# filter.net
KiCad netlist of a schematic drawn in Altium Designer
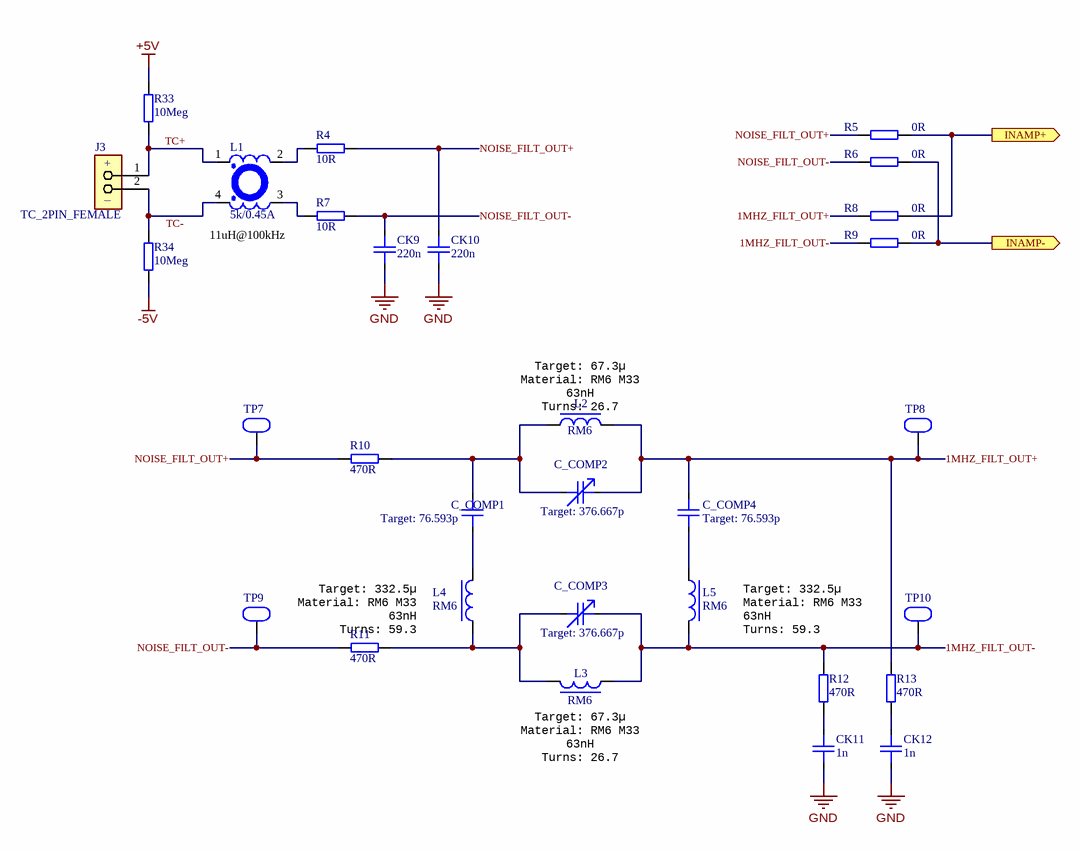
[diagram p0: filter.SchDoc]

(export (version "E")
  (design (tool "Eeschema 10.0.6"))
  (components
    (comp (ref "CK9")
      (value "220n")
      (footprint "CAPC1608X09N(SMC0603)")
      (description "C; 220n; 16V; 10%; X7R; ??;")
      (fields
        (field (name "MANUFACTURER") "TDK Corporation: C1608X7R1C224K080AC;;AVX Corporation: 0603YC224KAT2A;;Samsung: CL10B224KO8NNNC")
      )
      (libsource (lib "altium_sql") (part "CK"))
    )
    (comp (ref "CK10")
      (value "220n")
      (footprint "CAPC1608X09N(SMC0603)")
      (description "C; 220n; 16V; 10%; X7R; ??;")
      (fields
        (field (name "MANUFACTURER") "TDK Corporation: C1608X7R1C224K080AC;;AVX Corporation: 0603YC224KAT2A;;Samsung: CL10B224KO8NNNC")
      )
      (libsource (lib "altium_sql") (part "CK"))
    )
    (comp (ref "CK11")
      (value "1n")
      (footprint "CAPC2012X14N(SMC0805)")
      (description "C; 1n; 50V; 5%; NP0/C0G; ??;")
      (fields (field (name "MANUFACTURER") "YAGEO: CC0805JRNPO9BN102;;AVX: 0805 5A 102 JAT2A"))
      (libsource (lib "altium_sql") (part "CK"))
    )
    (comp (ref "CK12")
      (value "1n")
      (footprint "CAPC2012X14N(SMC0805)")
      (description "C; 1n; 50V; 5%; NP0/C0G; ??;")
      (fields (field (name "MANUFACTURER") "YAGEO: CC0805JRNPO9BN102;;AVX: 0805 5A 102 JAT2A"))
      (libsource (lib "altium_sql") (part "CK"))
    )
    (comp (ref "C_COMP1")
      (value "Target: 76.593p")
      (footprint "CAPC1005X06N(SMC0402)")
      (description "C; 470p; 50V; 1%; NP0/C0G; ??;")
      (fields (field (name "MANUFACTURER") "Kemet: C0402C471F5GAC7867;;Murata: GRM1555C1H471FA01D"))
      (libsource (lib "altium_sql") (part "CK"))
    )
    (comp (ref "C_COMP2")
      (value "Target: 376.667p")
      (footprint "CTSC3S")
      (description "3.5 - 10pF, 50V")
      (libsource (lib "custom-footprints") (part "CTSC3S"))
    )
    (comp (ref "C_COMP3")
      (value "Target: 376.667p")
      (footprint "CTSC3S")
      (description "3.5 - 10pF, 50V")
      (libsource (lib "custom-footprints") (part "CTSC3S"))
    )
    (comp (ref "C_COMP4")
      (value "Target: 76.593p")
      (footprint "CAPC1005X06N(SMC0402)")
      (description "C; 470p; 50V; 1%; NP0/C0G; ??;")
      (fields (field (name "MANUFACTURER") "Kemet: C0402C471F5GAC7867;;Murata: GRM1555C1H471FA01D"))
      (libsource (lib "altium_sql") (part "CK"))
    )
    (comp (ref "J3")
      (value "TC_2PIN_FEMALE")
      (footprint "TC_PCC-SMD")
      (description "Universal SMD thermocouple connector, 2 pin, Female")
      (libsource (lib "custom-footprints") (part "TC_2PIN_FEMALE"))
    )
    (comp (ref "L1")
      (value "5k/0.45A")
      (footprint "WE_744235110")
      (description "Flt; Common Mode Chokes; 0.8Ohm; 0.45A; 60V; 1x;")
      (fields (field (name "MANUFACTURER") "Würth: 744235110"))
      (libsource (lib "altium_sql") (part "L_COMP_43"))
    )
    (comp (ref "L2")
      (value "RM6")
      (footprint "INDP1616X10N")
      (description "L; 0.47uH; 1.7A; 30%; 0.101Ohm; Fe; 1x;")
      (fields (field (name "MANUFACTURER") "Wurth Elektronik: 784383130047"))
      (libsource (lib "altium_sql") (part "L"))
    )
    (comp (ref "L3")
      (value "RM6")
      (footprint "INDP1616X10N")
      (description "L; 0.47uH; 1.7A; 30%; 0.101Ohm; Fe; 1x;")
      (fields (field (name "MANUFACTURER") "Wurth Elektronik: 784383130047"))
      (libsource (lib "") (part "L_1"))
    )
    (comp (ref "L4")
      (value "RM6")
      (footprint "INDP1616X10N")
      (description "L; 0.47uH; 1.7A; 30%; 0.101Ohm; Fe; 1x;")
      (fields (field (name "MANUFACTURER") "Wurth Elektronik: 784383130047"))
      (libsource (lib "altium_sql") (part "L"))
    )
    (comp (ref "L5")
      (value "RM6")
      (footprint "INDP1616X10N")
      (description "L; 0.47uH; 1.7A; 30%; 0.101Ohm; Fe; 1x;")
      (fields (field (name "MANUFACTURER") "Wurth Elektronik: 784383130047"))
      (libsource (lib "") (part "L_1"))
    )
    (comp (ref "R4")
      (value "10R")
      (footprint "RESC2012X06N(SMR0805)")
      (description "R; 10R; 0.125W; 1%; 150V; Thick Film; ±200ppm/K; 1x;")
      (libsource (lib "altium_sql") (part "R"))
    )
    (comp (ref "R5")
      (value "0R")
      (footprint "RESC2012X06N(SMR0805)")
      (description "R; 0R; 0.125W; 1%; 150V; Thick Film; ±200ppm/K; 1x;")
      (fields
        (field (name "MANUFACTURER") "YAGEO: RC0805JR-100RL;;YAGEO: RC0805JR-130RL;;YAGEO: RC0805JR-070RL")
      )
      (libsource (lib "altium_sql") (part "R"))
    )
    (comp (ref "R6")
      (value "0R")
      (footprint "RESC2012X06N(SMR0805)")
      (description "R; 0R; 0.125W; 1%; 150V; Thick Film; ±200ppm/K; 1x;")
      (fields
        (field (name "MANUFACTURER") "YAGEO: RC0805JR-100RL;;YAGEO: RC0805JR-130RL;;YAGEO: RC0805JR-070RL")
      )
      (libsource (lib "altium_sql") (part "R"))
    )
    (comp (ref "R7")
      (value "10R")
      (footprint "RESC2012X06N(SMR0805)")
      (description "R; 10R; 0.125W; 1%; 150V; Thick Film; ±200ppm/K; 1x;")
      (libsource (lib "altium_sql") (part "R"))
    )
    (comp (ref "R8")
      (value "0R")
      (footprint "RESC2012X06N(SMR0805)")
      (description "R; 0R; 0.125W; 1%; 150V; Thick Film; ±200ppm/K; 1x;")
      (fields
        (field (name "MANUFACTURER") "YAGEO: RC0805JR-100RL;;YAGEO: RC0805JR-130RL;;YAGEO: RC0805JR-070RL")
      )
      (libsource (lib "altium_sql") (part "R"))
    )
    (comp (ref "R9")
      (value "0R")
      (footprint "RESC2012X06N(SMR0805)")
      (description "R; 0R; 0.125W; 1%; 150V; Thick Film; ±200ppm/K; 1x;")
      (fields
        (field (name "MANUFACTURER") "YAGEO: RC0805JR-100RL;;YAGEO: RC0805JR-130RL;;YAGEO: RC0805JR-070RL")
      )
      (libsource (lib "altium_sql") (part "R"))
    )
    (comp (ref "R10")
      (value "470R")
      (footprint "RESC1608X06N(SMR0603)")
      (description "R; 470R; 0.1W; 1%; 75V; Thick Film; ±100ppm/K; 1x;")
      (fields (field (name "MANUFACTURER") "Yageo: RC0603FR-07470RL;;Panasonic: ERJ3EKF4700V"))
      (libsource (lib "altium_sql") (part "R"))
    )
    (comp (ref "R11")
      (value "470R")
      (footprint "RESC1608X06N(SMR0603)")
      (description "R; 470R; 0.1W; 1%; 75V; Thick Film; ±100ppm/K; 1x;")
      (fields (field (name "MANUFACTURER") "Yageo: RC0603FR-07470RL;;Panasonic: ERJ3EKF4700V"))
      (libsource (lib "altium_sql") (part "R"))
    )
    (comp (ref "R12")
      (value "470R")
      (footprint "RESC1608X06N(SMR0603)")
      (description "R; 470R; 0.1W; 1%; 75V; Thick Film; ±100ppm/K; 1x;")
      (fields (field (name "MANUFACTURER") "Yageo: RC0603FR-07470RL;;Panasonic: ERJ3EKF4700V"))
      (libsource (lib "altium_sql") (part "R"))
    )
    (comp (ref "R13")
      (value "470R")
      (footprint "RESC1608X06N(SMR0603)")
      (description "R; 470R; 0.1W; 1%; 75V; Thick Film; ±100ppm/K; 1x;")
      (fields (field (name "MANUFACTURER") "Yageo: RC0603FR-07470RL;;Panasonic: ERJ3EKF4700V"))
      (libsource (lib "altium_sql") (part "R"))
    )
    (comp (ref "R33")
      (value "10Meg")
      (footprint "RESC2012X06N(SMR0805)")
      (description "R; 10Meg; 0.125W; 5%; 150V; Thick Film; ±100ppm/K; 1x;")
      (fields
        (field (name "MANUFACTURER") "YAGEO: RC0805JR-0710ML;;BC Components: MCU0805-50 1% P5 10M;;PANASONIC: ERJ 6GE Y J 106 V")
      )
      (libsource (lib "altium_sql") (part "R"))
    )
    (comp (ref "R34")
      (value "10Meg")
      (footprint "RESC2012X06N(SMR0805)")
      (description "R; 10Meg; 0.125W; 5%; 150V; Thick Film; ±100ppm/K; 1x;")
      (fields
        (field (name "MANUFACTURER") "YAGEO: RC0805JR-0710ML;;BC Components: MCU0805-50 1% P5 10M;;PANASONIC: ERJ 6GE Y J 106 V")
      )
      (libsource (lib "altium_sql") (part "R"))
    )
    (comp (ref "TP7")
      (value "Test Point")
      (footprint "SMD_Testpoint_Onelayer")
      (description "Con; Test Point; 1x; PCB; ??; ??V; ??A; ??; Tin; Contact;")
      (fields (field (name "MANUFACTURER") "Harwin: S1751-46R") (field (name "CONNECTOR_PART") "Contact"))
      (libsource (lib "altium_sql") (part "EJ+TESTPOINTXX0"))
    )
    (comp (ref "TP8")
      (value "Test Point")
      (footprint "SMD_Testpoint_Onelayer")
      (description "Con; Test Point; 1x; PCB; ??; ??V; ??A; ??; Tin; Contact;")
      (fields (field (name "MANUFACTURER") "Harwin: S1751-46R") (field (name "CONNECTOR_PART") "Contact"))
      (libsource (lib "altium_sql") (part "EJ+TESTPOINTXX0"))
    )
    (comp (ref "TP9")
      (value "Test Point")
      (footprint "SMD_Testpoint_Onelayer")
      (description "Con; Test Point; 1x; PCB; ??; ??V; ??A; ??; Tin; Contact;")
      (fields (field (name "MANUFACTURER") "Harwin: S1751-46R") (field (name "CONNECTOR_PART") "Contact"))
      (libsource (lib "altium_sql") (part "EJ+TESTPOINTXX0"))
    )
    (comp (ref "TP10")
      (value "Test Point")
      (footprint "SMD_Testpoint_Onelayer")
      (description "Con; Test Point; 1x; PCB; ??; ??V; ??A; ??; Tin; Contact;")
      (fields (field (name "MANUFACTURER") "Harwin: S1751-46R") (field (name "CONNECTOR_PART") "Contact"))
      (libsource (lib "altium_sql") (part "EJ+TESTPOINTXX0"))
    )
  )
  (nets
    (net (code "1") (name "+5V") (class "Default")
      (node (ref "R33") (pin "2") (pinfunction "2_2") (pintype "passive"))
    )
    (net (code "2") (name "-5V") (class "Default")
      (node (ref "R34") (pin "1") (pinfunction "1_1") (pintype "passive"))
    )
    (net (code "3") (name "/1MHZ_FILT_OUT+") (class "Default")
      (node (ref "C_COMP2") (pin "1") (pinfunction "1_1") (pintype "passive"))
      (node (ref "C_COMP4") (pin "1") (pinfunction "1_1") (pintype "passive"))
      (node (ref "L2") (pin "2") (pinfunction "L1B_2") (pintype "passive"))
      (node (ref "R13") (pin "2") (pinfunction "2_2") (pintype "passive"))
      (node (ref "R8") (pin "1") (pinfunction "1_1") (pintype "passive"))
      (node (ref "TP8") (pin "1") (pintype "passive"))
    )
    (net (code "4") (name "/1MHZ_FILT_OUT-") (class "Default")
      (node (ref "C_COMP3") (pin "1") (pinfunction "1_1") (pintype "passive"))
      (node (ref "L3") (pin "2") (pinfunction "L1B_2") (pintype "passive"))
      (node (ref "L5") (pin "1") (pinfunction "L1A_1") (pintype "passive"))
      (node (ref "R12") (pin "2") (pinfunction "2_2") (pintype "passive"))
      (node (ref "R9") (pin "1") (pinfunction "1_1") (pintype "passive"))
      (node (ref "TP10") (pin "1") (pintype "passive"))
    )
    (net (code "5") (name "/INAMP+") (class "Default")
      (node (ref "R5") (pin "2") (pinfunction "2_2") (pintype "passive"))
      (node (ref "R8") (pin "2") (pinfunction "2_2") (pintype "passive"))
    )
    (net (code "6") (name "/INAMP-") (class "Default")
      (node (ref "R6") (pin "2") (pinfunction "2_2") (pintype "passive"))
      (node (ref "R9") (pin "2") (pinfunction "2_2") (pintype "passive"))
    )
    (net (code "7") (name "/NOISE_FILT_OUT+") (class "Default")
      (node (ref "CK10") (pin "1") (pinfunction "1_1") (pintype "passive"))
      (node (ref "R10") (pin "1") (pinfunction "1_1") (pintype "passive"))
      (node (ref "R4") (pin "1") (pinfunction "1_1") (pintype "passive"))
      (node (ref "R5") (pin "1") (pinfunction "1_1") (pintype "passive"))
      (node (ref "TP7") (pin "1") (pintype "passive"))
    )
    (net (code "8") (name "/NOISE_FILT_OUT-") (class "Default")
      (node (ref "CK9") (pin "1") (pinfunction "1_1") (pintype "passive"))
      (node (ref "R11") (pin "1") (pinfunction "1_1") (pintype "passive"))
      (node (ref "R6") (pin "1") (pinfunction "1_1") (pintype "passive"))
      (node (ref "R7") (pin "2") (pinfunction "2_2") (pintype "passive"))
      (node (ref "TP9") (pin "1") (pintype "passive"))
    )
    (net (code "9") (name "/TC+") (class "Default")
      (node (ref "J3") (pin "1") (pinfunction "1_1") (pintype "passive"))
      (node (ref "L1") (pin "1") (pinfunction "L1A_1") (pintype "passive"))
      (node (ref "R33") (pin "1") (pinfunction "1_1") (pintype "passive"))
    )
    (net (code "10") (name "/TC-") (class "Default")
      (node (ref "J3") (pin "2") (pinfunction "2_2") (pintype "passive"))
      (node (ref "L1") (pin "4") (pinfunction "L2B_4") (pintype "passive"))
      (node (ref "R34") (pin "2") (pinfunction "2_2") (pintype "passive"))
    )
    (net (code "11") (name "GND") (class "Default")
      (node (ref "CK10") (pin "2") (pinfunction "2_2") (pintype "passive"))
      (node (ref "CK11") (pin "1") (pinfunction "1_1") (pintype "passive"))
      (node (ref "CK12") (pin "1") (pinfunction "1_1") (pintype "passive"))
      (node (ref "CK9") (pin "2") (pinfunction "2_2") (pintype "passive"))
    )
    (net (code "12") (name "Net-(CK11-Pad2)") (class "Default")
      (node (ref "CK11") (pin "2") (pinfunction "2_2") (pintype "passive"))
      (node (ref "R12") (pin "1") (pinfunction "1_1") (pintype "passive"))
    )
    (net (code "13") (name "Net-(CK12-Pad2)") (class "Default")
      (node (ref "CK12") (pin "2") (pinfunction "2_2") (pintype "passive"))
      (node (ref "R13") (pin "1") (pinfunction "1_1") (pintype "passive"))
    )
    (net (code "14") (name "Net-(L1-L1B)") (class "Default")
      (node (ref "L1") (pin "2") (pinfunction "L1B_2") (pintype "passive"))
      (node (ref "R4") (pin "2") (pinfunction "2_2") (pintype "passive"))
    )
    (net (code "15") (name "Net-(L1-L2A)") (class "Default")
      (node (ref "L1") (pin "3") (pinfunction "L2A_3") (pintype "passive"))
      (node (ref "R7") (pin "1") (pinfunction "1_1") (pintype "passive"))
    )
    (net (code "16") (name "Net-(L2-L1A)") (class "Default")
      (node (ref "C_COMP1") (pin "1") (pinfunction "1_1") (pintype "passive"))
      (node (ref "C_COMP2") (pin "2") (pinfunction "2_2") (pintype "passive"))
      (node (ref "L2") (pin "1") (pinfunction "L1A_1") (pintype "passive"))
      (node (ref "R10") (pin "2") (pinfunction "2_2") (pintype "passive"))
    )
    (net (code "17") (name "Net-(L3-L1A)") (class "Default")
      (node (ref "C_COMP3") (pin "2") (pinfunction "2_2") (pintype "passive"))
      (node (ref "L3") (pin "1") (pinfunction "L1A_1") (pintype "passive"))
      (node (ref "L4") (pin "1") (pinfunction "L1A_1") (pintype "passive"))
      (node (ref "R11") (pin "2") (pinfunction "2_2") (pintype "passive"))
    )
    (net (code "18") (name "Net-(L4-L1B)") (class "Default")
      (node (ref "C_COMP1") (pin "2") (pinfunction "2_2") (pintype "passive"))
      (node (ref "L4") (pin "2") (pinfunction "L1B_2") (pintype "passive"))
    )
    (net (code "19") (name "Net-(L5-L1B)") (class "Default")
      (node (ref "C_COMP4") (pin "2") (pinfunction "2_2") (pintype "passive"))
      (node (ref "L5") (pin "2") (pinfunction "L1B_2") (pintype "passive"))
    )
  )
)
